# USB2TTL485.net
KiCad netlist of a schematic drawn in EAGLE
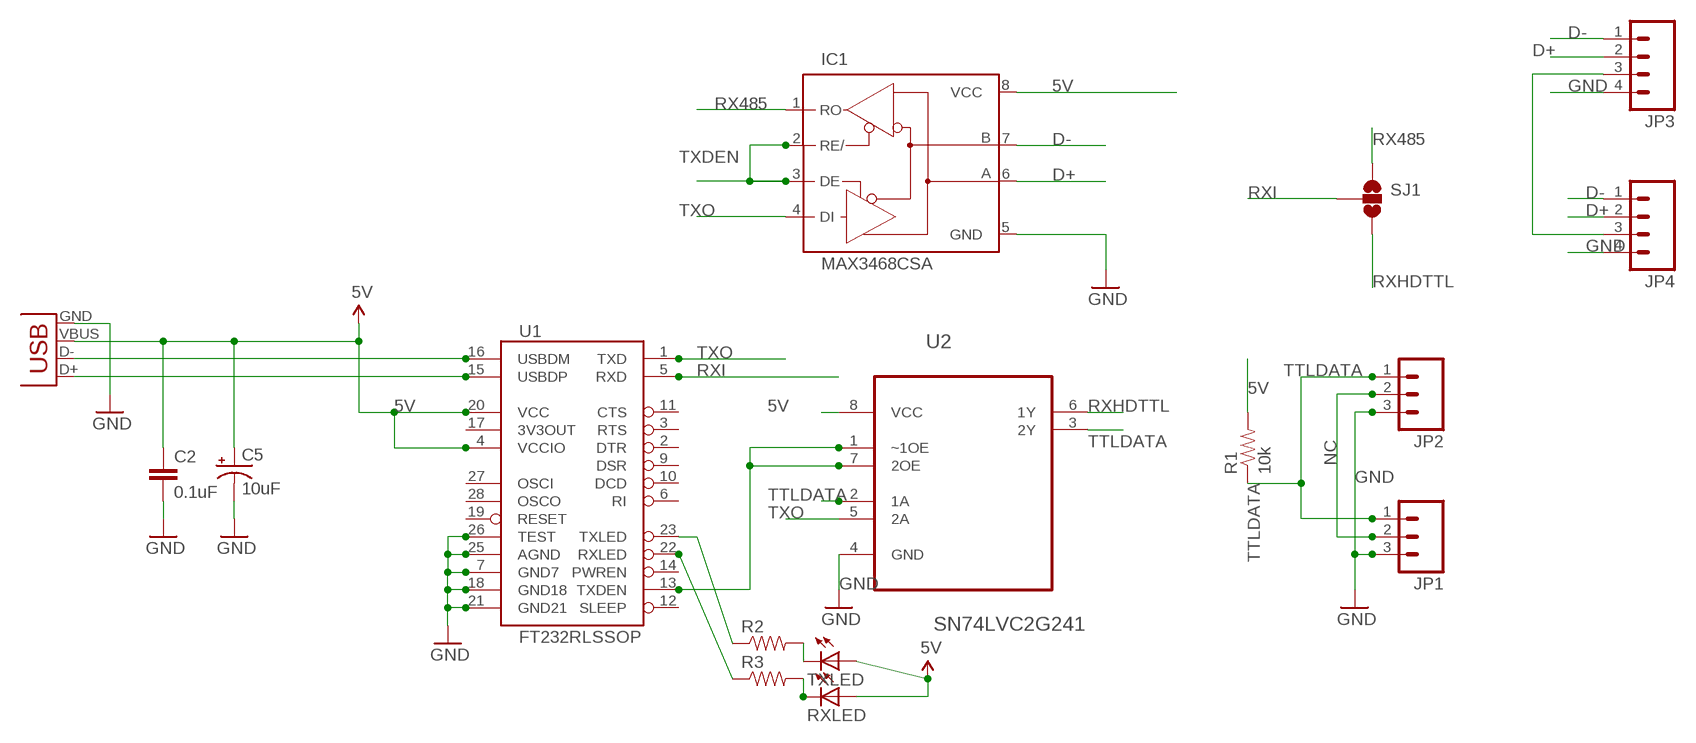
[diagram p0: schematic, sheet 1]

(export (version "E")
  (design (tool "Eeschema 10.0.6"))
  (components
    (comp (ref "C2")
      (value "0.1uF")
      (footprint "eagle-import:0402-CAP")
      (libsource (lib "eagle-import") (part "CAP0402-CAP"))
    )
    (comp (ref "C5")
      (value "10uF")
      (footprint "eagle-import:EIA3216")
      (libsource (lib "eagle-import") (part "CAP_POL1206"))
    )
    (comp (ref "IC1")
      (value "MAX3468CSA")
      (footprint "eagle-import:SO08")
      (fields (field (name "MPN") "MAX3468CSA+"))
      (libsource (lib "eagle-import") (part "MAX34SA68C"))
    )
    (comp (ref "JP1")
      (value "M03LOCK_LONGPADS")
      (footprint "eagle-import:1X03_LOCK_LONGPADS")
      (libsource (lib "eagle-import") (part "M03LOCK_LONGPADS"))
    )
    (comp (ref "JP2")
      (value "M03LOCK_LONGPADS")
      (footprint "eagle-import:1X03_LOCK_LONGPADS")
      (libsource (lib "eagle-import") (part "M03LOCK_LONGPADS"))
    )
    (comp (ref "JP3")
      (value "M04LOCK_LONGPADS")
      (footprint "eagle-import:1X04_LOCK_LONGPADS")
      (libsource (lib "eagle-import") (part "M04LOCK_LONGPADS"))
    )
    (comp (ref "JP4")
      (value "M04LOCK_LONGPADS")
      (footprint "eagle-import:1X04_LOCK_LONGPADS")
      (libsource (lib "eagle-import") (part "M04LOCK_LONGPADS"))
    )
    (comp (ref "R1")
      (value "10k")
      (footprint "eagle-import:0603-RES")
      (libsource (lib "eagle-import") (part "custom-cap0603_RESISTOR0603-RES"))
    )
    (comp (ref "R2")
      (value "RESISTOR0603-RES")
      (footprint "eagle-import:0603-RES")
      (libsource (lib "eagle-import") (part "RESISTOR0603-RES"))
    )
    (comp (ref "R3")
      (value "RESISTOR0603-RES")
      (footprint "eagle-import:0603-RES")
      (libsource (lib "eagle-import") (part "RESISTOR0603-RES"))
    )
    (comp (ref "RXLED")
      (value "LED0603")
      (footprint "eagle-import:LED-0603")
      (libsource (lib "eagle-import") (part "LED0603"))
    )
    (comp (ref "SJ1")
      (value "SOLDERJUMPER_2WAYT")
      (footprint "eagle-import:SJ_2")
      (libsource (lib "eagle-import") (part "SOLDERJUMPER_2WAYT"))
    )
    (comp (ref "TXLED")
      (value "LED0603")
      (footprint "eagle-import:LED-0603")
      (libsource (lib "eagle-import") (part "LED0603"))
    )
    (comp (ref "U1")
      (value "FT232RLSSOP")
      (footprint "eagle-import:SSOP28DB")
      (libsource (lib "eagle-import") (part "FT232RLSSOP"))
    )
    (comp (ref "U2")
      (value "SN74LVC2G241")
      (footprint "eagle-import:SOP65P400X130-8N")
      (libsource (lib "eagle-import") (part "SN74LVC2G241"))
    )
    (comp (ref "X2")
      (value "USB-SMD-NS")
      (footprint "eagle-import:USB-MINIB-NOSTOP")
      (libsource (lib "eagle-import") (part "USB-SMD-NS"))
    )
  )
  (nets
    (net (code "1") (name "/D+") (class "Default")
      (node (ref "IC1") (pin "6") (pinfunction "A_6") (pintype "passive"))
      (node (ref "JP3") (pin "2") (pinfunction "2_2") (pintype "passive"))
      (node (ref "JP4") (pin "2") (pinfunction "2_2") (pintype "passive"))
    )
    (net (code "2") (name "/D-") (class "Default")
      (node (ref "IC1") (pin "7") (pinfunction "B_7") (pintype "passive"))
      (node (ref "JP3") (pin "1") (pinfunction "1_1") (pintype "passive"))
      (node (ref "JP4") (pin "1") (pinfunction "1_1") (pintype "passive"))
    )
    (net (code "3") (name "/NC") (class "Default")
      (node (ref "JP1") (pin "2") (pinfunction "2_2") (pintype "passive"))
      (node (ref "JP2") (pin "2") (pinfunction "2_2") (pintype "passive"))
    )
    (net (code "4") (name "/RX485") (class "Default")
      (node (ref "IC1") (pin "1") (pinfunction "RO_1") (pintype "output"))
      (node (ref "SJ1") (pin "1") (pinfunction "1_1") (pintype "passive"))
    )
    (net (code "5") (name "/RXHDTTL") (class "Default")
      (node (ref "SJ1") (pin "3") (pinfunction "3_3") (pintype "passive"))
      (node (ref "U2") (pin "6") (pinfunction "1Y_6") (pintype "output"))
    )
    (net (code "6") (name "/RXI") (class "Default")
      (node (ref "SJ1") (pin "2") (pinfunction "2_2") (pintype "passive"))
      (node (ref "U1") (pin "5") (pinfunction "RXD_5") (pintype "input"))
    )
    (net (code "7") (name "/TTLDATA") (class "Default")
      (node (ref "JP1") (pin "1") (pinfunction "1_1") (pintype "passive"))
      (node (ref "JP2") (pin "1") (pinfunction "1_1") (pintype "passive"))
      (node (ref "R1") (pin "1") (pinfunction "1_1") (pintype "passive"))
      (node (ref "U2") (pin "2") (pinfunction "1A_2") (pintype "input"))
      (node (ref "U2") (pin "3") (pinfunction "2Y_3") (pintype "output"))
    )
    (net (code "8") (name "/TXDEN") (class "Default")
      (node (ref "IC1") (pin "2") (pinfunction "RE/_2") (pintype "input"))
      (node (ref "IC1") (pin "3") (pinfunction "DE_3") (pintype "input"))
      (node (ref "U1") (pin "13") (pinfunction "TXDEN_13") (pintype "input"))
      (node (ref "U2") (pin "1") (pinfunction "~{1OE}_1") (pintype "input"))
      (node (ref "U2") (pin "7") (pinfunction "2OE_7") (pintype "input"))
    )
    (net (code "9") (name "/TXO") (class "Default")
      (node (ref "IC1") (pin "4") (pinfunction "DI_4") (pintype "input"))
      (node (ref "U1") (pin "1") (pinfunction "TXD_1") (pintype "output"))
      (node (ref "U2") (pin "5") (pinfunction "2A_5") (pintype "input"))
    )
    (net (code "10") (name "5V") (class "Default")
      (node (ref "C2") (pin "1") (pinfunction "1_1") (pintype "passive"))
      (node (ref "C5") (pin "A") (pinfunction "+_A") (pintype "passive"))
      (node (ref "IC1") (pin "8") (pinfunction "VCC_8") (pintype "power_in"))
      (node (ref "R1") (pin "2") (pinfunction "2_2") (pintype "passive"))
      (node (ref "RXLED") (pin "A") (pinfunction "A_A") (pintype "passive"))
      (node (ref "TXLED") (pin "A") (pinfunction "A_A") (pintype "passive"))
      (node (ref "U1") (pin "20") (pinfunction "VCC_20") (pintype "power_in"))
      (node (ref "U1") (pin "4") (pinfunction "VCCIO_4") (pintype "power_in"))
      (node (ref "U2") (pin "8") (pinfunction "VCC_8") (pintype "power_in"))
      (node (ref "X2") (pin "VBUS") (pinfunction "VBUS_VBUS") (pintype "bidirectional"))
    )
    (net (code "11") (name "GND") (class "Default")
      (node (ref "C2") (pin "2") (pinfunction "2_2") (pintype "passive"))
      (node (ref "C5") (pin "C") (pinfunction "-_C") (pintype "passive"))
      (node (ref "IC1") (pin "5") (pinfunction "GND_5") (pintype "power_in"))
      (node (ref "JP1") (pin "3") (pinfunction "3_3") (pintype "passive"))
      (node (ref "JP2") (pin "3") (pinfunction "3_3") (pintype "passive"))
      (node (ref "JP3") (pin "4") (pinfunction "4_4") (pintype "passive"))
      (node (ref "JP4") (pin "4") (pinfunction "4_4") (pintype "passive"))
      (node (ref "U1") (pin "18") (pinfunction "GND18_18") (pintype "power_in"))
      (node (ref "U1") (pin "21") (pinfunction "GND21_21") (pintype "power_in"))
      (node (ref "U1") (pin "25") (pinfunction "AGND_25") (pintype "power_in"))
      (node (ref "U1") (pin "26") (pinfunction "TEST_26") (pintype "input"))
      (node (ref "U1") (pin "7") (pinfunction "GND7_7") (pintype "power_in"))
      (node (ref "U2") (pin "4") (pinfunction "GND_4") (pintype "passive"))
      (node (ref "X2") (pin "GND") (pinfunction "GND_GND") (pintype "bidirectional"))
    )
    (net (code "12") (name "Net-(JP3-Pad3)") (class "Default")
      (node (ref "JP3") (pin "3") (pinfunction "3_3") (pintype "passive"))
      (node (ref "JP4") (pin "3") (pinfunction "3_3") (pintype "passive"))
    )
    (net (code "13") (name "Net-(R2-Pad2)") (class "Default")
      (node (ref "R2") (pin "2") (pinfunction "2_2") (pintype "passive"))
      (node (ref "TXLED") (pin "C") (pinfunction "C_C") (pintype "passive"))
    )
    (net (code "14") (name "Net-(R3-Pad2)") (class "Default")
      (node (ref "R3") (pin "2") (pinfunction "2_2") (pintype "passive"))
      (node (ref "RXLED") (pin "C") (pinfunction "C_C") (pintype "passive"))
    )
    (net (code "15") (name "Net-(U1-RXLED)") (class "Default")
      (node (ref "R3") (pin "1") (pinfunction "1_1") (pintype "passive"))
      (node (ref "U1") (pin "22") (pinfunction "RXLED_22") (pintype "input"))
    )
    (net (code "16") (name "Net-(U1-TXLED)") (class "Default")
      (node (ref "R2") (pin "1") (pinfunction "1_1") (pintype "passive"))
      (node (ref "U1") (pin "23") (pinfunction "TXLED_23") (pintype "input"))
    )
    (net (code "17") (name "Net-(U1-USBDM)") (class "Default")
      (node (ref "U1") (pin "16") (pinfunction "USBDM_16") (pintype "bidirectional"))
      (node (ref "X2") (pin "D-") (pinfunction "D-_D-") (pintype "bidirectional"))
    )
    (net (code "18") (name "Net-(U1-USBDP)") (class "Default")
      (node (ref "U1") (pin "15") (pinfunction "USBDP_15") (pintype "bidirectional"))
      (node (ref "X2") (pin "D+") (pinfunction "D+_D+") (pintype "bidirectional"))
    )
    (net (code "19") (name "unconnected-(U1-3V3OUT-Pad17)") (class "Default")
      (node (ref "U1") (pin "17") (pinfunction "3V3OUT_17") (pintype "output"))
    )
    (net (code "20") (name "unconnected-(U1-CTS-Pad11)") (class "Default")
      (node (ref "U1") (pin "11") (pinfunction "CTS_11") (pintype "input"))
    )
    (net (code "21") (name "unconnected-(U1-DCD-Pad10)") (class "Default")
      (node (ref "U1") (pin "10") (pinfunction "DCD_10") (pintype "input"))
    )
    (net (code "22") (name "unconnected-(U1-DSR-Pad9)") (class "Default")
      (node (ref "U1") (pin "9") (pinfunction "DSR_9") (pintype "input"))
    )
    (net (code "23") (name "unconnected-(U1-DTR-Pad2)") (class "Default")
      (node (ref "U1") (pin "2") (pinfunction "DTR_2") (pintype "output"))
    )
    (net (code "24") (name "unconnected-(U1-OSCI-Pad27)") (class "Default")
      (node (ref "U1") (pin "27") (pinfunction "OSCI_27") (pintype "input"))
    )
    (net (code "25") (name "unconnected-(U1-OSCO-Pad28)") (class "Default")
      (node (ref "U1") (pin "28") (pinfunction "OSCO_28") (pintype "output"))
    )
    (net (code "26") (name "unconnected-(U1-PWREN-Pad14)") (class "Default")
      (node (ref "U1") (pin "14") (pinfunction "PWREN_14") (pintype "input"))
    )
    (net (code "27") (name "unconnected-(U1-RESET-Pad19)") (class "Default")
      (node (ref "U1") (pin "19") (pinfunction "RESET_19") (pintype "input"))
    )
    (net (code "28") (name "unconnected-(U1-RI-Pad6)") (class "Default")
      (node (ref "U1") (pin "6") (pinfunction "RI_6") (pintype "input"))
    )
    (net (code "29") (name "unconnected-(U1-RTS-Pad3)") (class "Default")
      (node (ref "U1") (pin "3") (pinfunction "RTS_3") (pintype "output"))
    )
    (net (code "30") (name "unconnected-(U1-SLEEP-Pad12)") (class "Default")
      (node (ref "U1") (pin "12") (pinfunction "SLEEP_12") (pintype "input"))
    )
  )
)
